# USB_HUB.net
KiCad netlist of a schematic drawn in EasyEDA Pro
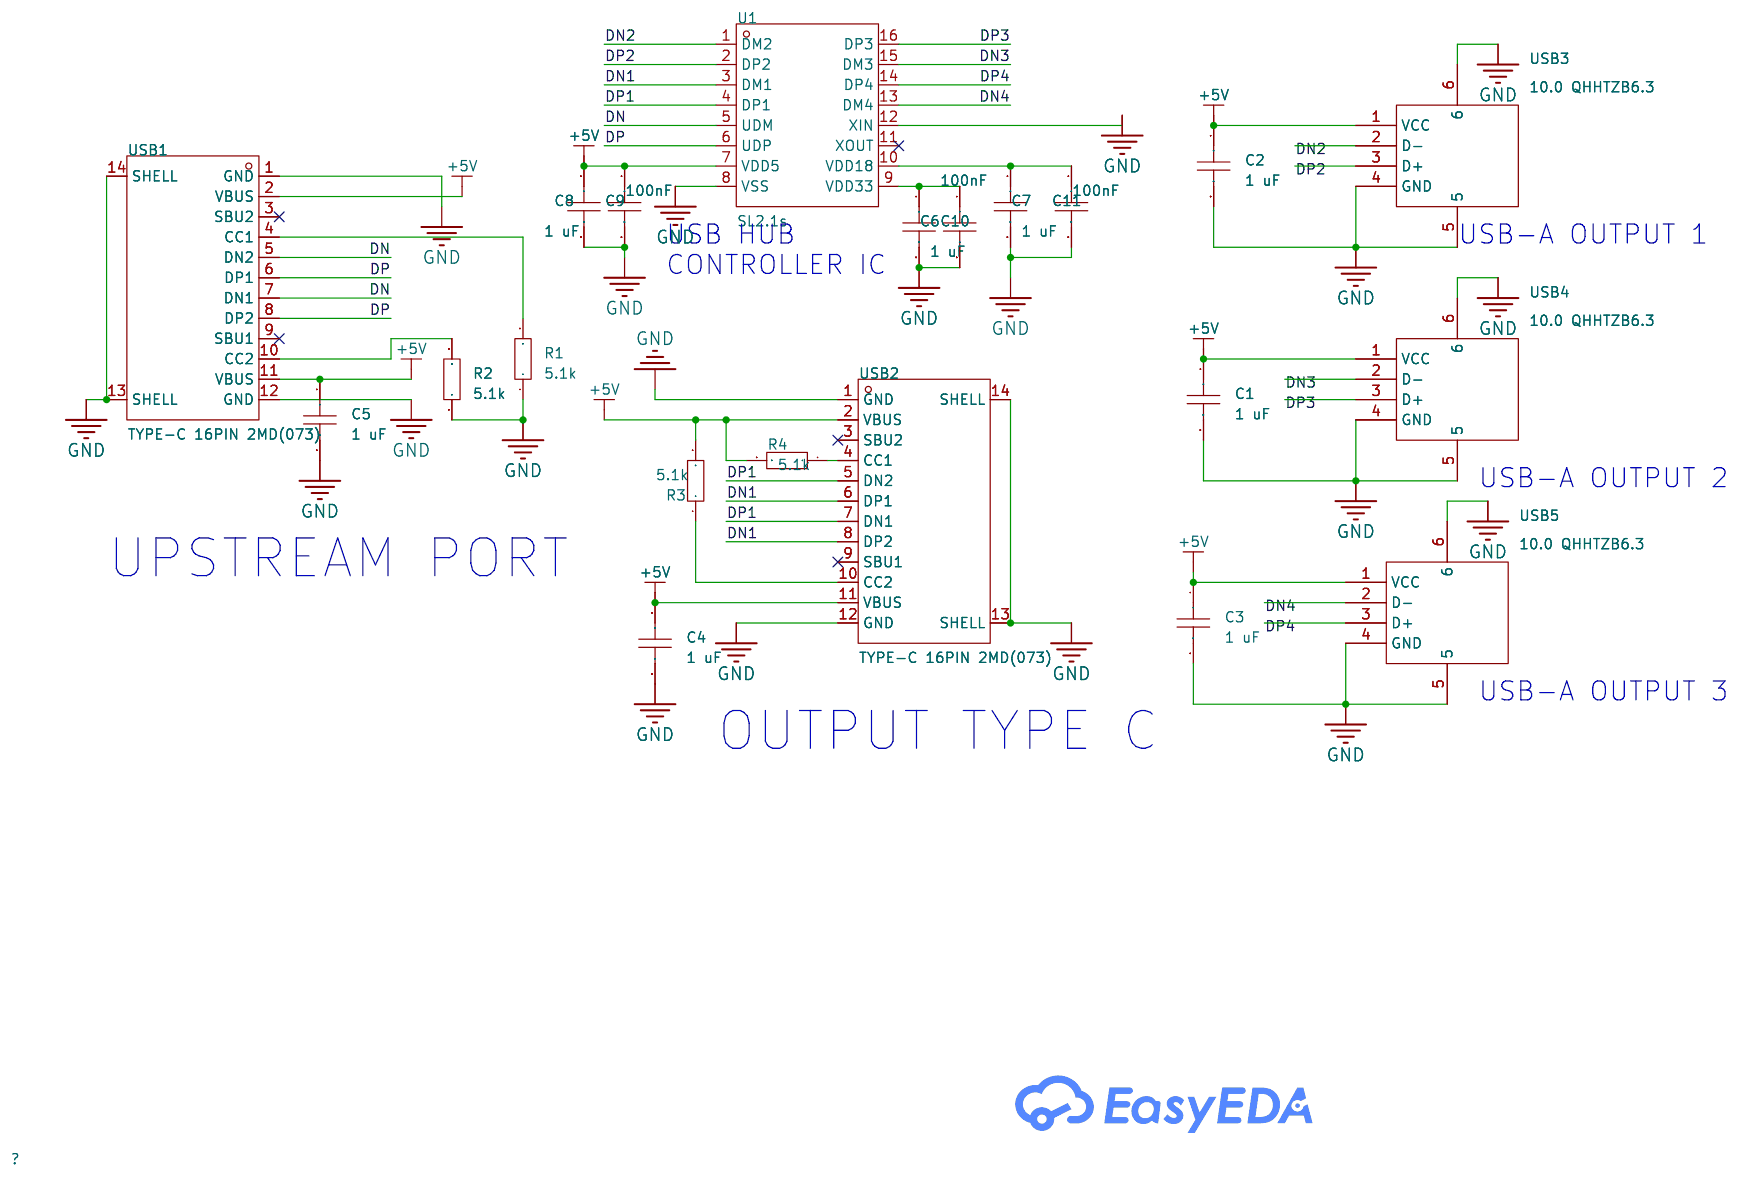
[diagram p0: schematic sheet]

(export (version "E")
  (design (tool "Eeschema 10.0.6"))
  (components
    (comp (ref "C1")
      (value "1 uF")
      (footprint "easyedapro:C0603")
      (libsource (lib "easyedapro") (part "CAP"))
    )
    (comp (ref "C2")
      (value "1 uF")
      (footprint "easyedapro:C0603")
      (libsource (lib "easyedapro") (part "CAP"))
    )
    (comp (ref "C3")
      (value "1 uF")
      (footprint "easyedapro:C0603")
      (libsource (lib "easyedapro") (part "CAP"))
    )
    (comp (ref "C4")
      (value "1 uF")
      (footprint "easyedapro:C0603")
      (libsource (lib "easyedapro") (part "CAP"))
    )
    (comp (ref "C5")
      (value "1 uF")
      (footprint "easyedapro:C0603")
      (libsource (lib "easyedapro") (part "CAP"))
    )
    (comp (ref "C6")
      (value "1 uF")
      (footprint "easyedapro:C0603")
      (libsource (lib "easyedapro") (part "CAP"))
    )
    (comp (ref "C7")
      (value "1 uF")
      (footprint "easyedapro:C0603")
      (libsource (lib "easyedapro") (part "CAP"))
    )
    (comp (ref "C8")
      (value "1 uF")
      (footprint "easyedapro:C0603")
      (libsource (lib "easyedapro") (part "CAP"))
    )
    (comp (ref "C9")
      (value "100nF")
      (footprint "easyedapro:C0603")
      (libsource (lib "easyedapro") (part "CAP"))
    )
    (comp (ref "C10")
      (value "100nF")
      (footprint "easyedapro:C0603")
      (libsource (lib "easyedapro") (part "CAP"))
    )
    (comp (ref "C11")
      (value "100nF")
      (footprint "easyedapro:C0603")
      (libsource (lib "easyedapro") (part "CAP"))
    )
    (comp (ref "R1")
      (value "5.1k")
      (footprint "easyedapro:R0603")
      (libsource (lib "easyedapro") (part "Res"))
    )
    (comp (ref "R2")
      (value "5.1k")
      (footprint "easyedapro:R0603")
      (libsource (lib "easyedapro") (part "Res"))
    )
    (comp (ref "R3")
      (value "5.1k")
      (footprint "easyedapro:R0603")
      (libsource (lib "easyedapro") (part "Res"))
    )
    (comp (ref "R4")
      (value "5.1k")
      (footprint "easyedapro:R0603")
      (libsource (lib "easyedapro") (part "Res"))
    )
    (comp (ref "U1")
      (value "SL2.1s")
      (footprint "easyedapro:SSOP-16_L4.6-W2.6-P0.53-LS4.0-BL")
      (fields (field (name "Manufacturer") "CoreChips(和芯润德)"))
      (libsource (lib "easyedapro") (part "SL2.1S"))
    )
    (comp (ref "USB1")
      (value "TYPE-C 16PIN 2MD(073)")
      (footprint "easyedapro:USB-C-SMD_TYPE-C-6PIN-2MD-073")
      (fields (field (name "Manufacturer") "SHOU HAN(首韩)"))
      (libsource (lib "easyedapro") (part "TYPE-C 16PIN 2MD(073)"))
    )
    (comp (ref "USB2")
      (value "TYPE-C 16PIN 2MD(073)")
      (footprint "easyedapro:USB-C-SMD_TYPE-C-6PIN-2MD-073")
      (fields (field (name "Manufacturer") "SHOU HAN(首韩)"))
      (libsource (lib "easyedapro") (part "TYPE-C 16PIN 2MD(073)"))
    )
    (comp (ref "USB3")
      (value "10.0 QHHTZB6.3")
      (footprint "easyedapro:USB-A-TH_10.0QHHTZB6.3")
      (fields (field (name "Manufacturer") "SHOU HAN(首韩)"))
      (libsource (lib "easyedapro") (part "10.0 QHHTZB6.3"))
    )
    (comp (ref "USB4")
      (value "10.0 QHHTZB6.3")
      (footprint "easyedapro:USB-A-TH_10.0QHHTZB6.3")
      (fields (field (name "Manufacturer") "SHOU HAN(首韩)"))
      (libsource (lib "easyedapro") (part "10.0 QHHTZB6.3"))
    )
    (comp (ref "USB5")
      (value "10.0 QHHTZB6.3")
      (footprint "easyedapro:USB-A-TH_10.0QHHTZB6.3")
      (fields (field (name "Manufacturer") "SHOU HAN(首韩)"))
      (libsource (lib "easyedapro") (part "10.0 QHHTZB6.3"))
    )
  )
  (nets
    (net (code "1") (name "+5V") (class "Default")
      (node (ref "C1") (pin "1") (pinfunction "1_1") (pintype "input"))
      (node (ref "C2") (pin "1") (pinfunction "1_1") (pintype "input"))
      (node (ref "C3") (pin "1") (pinfunction "1_1") (pintype "input"))
      (node (ref "C4") (pin "1") (pinfunction "1_1") (pintype "input"))
      (node (ref "C5") (pin "1") (pinfunction "1_1") (pintype "input"))
      (node (ref "C8") (pin "1") (pinfunction "1_1") (pintype "input"))
      (node (ref "C9") (pin "1") (pinfunction "1_1") (pintype "input"))
      (node (ref "R3") (pin "2") (pinfunction "2_2") (pintype "input"))
      (node (ref "R4") (pin "2") (pinfunction "2_2") (pintype "input"))
      (node (ref "U1") (pin "7") (pinfunction "VDD5_7") (pintype "unspecified"))
      (node (ref "USB1") (pin "11") (pinfunction "VBUS_11") (pintype "unspecified"))
      (node (ref "USB1") (pin "2") (pinfunction "VBUS_2") (pintype "unspecified"))
      (node (ref "USB2") (pin "11") (pinfunction "VBUS_11") (pintype "unspecified"))
      (node (ref "USB2") (pin "2") (pinfunction "VBUS_2") (pintype "unspecified"))
      (node (ref "USB3") (pin "1") (pinfunction "VCC_1") (pintype "unspecified"))
      (node (ref "USB4") (pin "1") (pinfunction "VCC_1") (pintype "unspecified"))
      (node (ref "USB5") (pin "1") (pinfunction "VCC_1") (pintype "unspecified"))
    )
    (net (code "2") (name "/DN") (class "Default")
      (node (ref "U1") (pin "5") (pinfunction "UDM_5") (pintype "unspecified"))
      (node (ref "USB1") (pin "5") (pinfunction "DN2_5") (pintype "unspecified"))
      (node (ref "USB1") (pin "7") (pinfunction "DN1_7") (pintype "unspecified"))
    )
    (net (code "3") (name "/DN1") (class "Default")
      (node (ref "U1") (pin "3") (pinfunction "DM1_3") (pintype "unspecified"))
      (node (ref "USB2") (pin "6") (pinfunction "DP1_6") (pintype "unspecified"))
      (node (ref "USB2") (pin "8") (pinfunction "DP2_8") (pintype "unspecified"))
    )
    (net (code "4") (name "/DN2") (class "Default")
      (node (ref "U1") (pin "1") (pinfunction "DM2_1") (pintype "unspecified"))
      (node (ref "USB3") (pin "2") (pinfunction "D-_2") (pintype "unspecified"))
    )
    (net (code "5") (name "/DN3") (class "Default")
      (node (ref "U1") (pin "15") (pinfunction "DM3_15") (pintype "unspecified"))
      (node (ref "USB4") (pin "2") (pinfunction "D-_2") (pintype "unspecified"))
    )
    (net (code "6") (name "/DN4") (class "Default")
      (node (ref "U1") (pin "13") (pinfunction "DM4_13") (pintype "unspecified"))
      (node (ref "USB5") (pin "2") (pinfunction "D-_2") (pintype "unspecified"))
    )
    (net (code "7") (name "/DP") (class "Default")
      (node (ref "U1") (pin "6") (pinfunction "UDP_6") (pintype "unspecified"))
      (node (ref "USB1") (pin "6") (pinfunction "DP1_6") (pintype "unspecified"))
      (node (ref "USB1") (pin "8") (pinfunction "DP2_8") (pintype "unspecified"))
    )
    (net (code "8") (name "/DP1") (class "Default")
      (node (ref "U1") (pin "4") (pinfunction "DP1_4") (pintype "unspecified"))
      (node (ref "USB2") (pin "5") (pinfunction "DN2_5") (pintype "unspecified"))
      (node (ref "USB2") (pin "7") (pinfunction "DN1_7") (pintype "unspecified"))
    )
    (net (code "9") (name "/DP2") (class "Default")
      (node (ref "U1") (pin "2") (pinfunction "DP2_2") (pintype "unspecified"))
      (node (ref "USB3") (pin "3") (pinfunction "D+_3") (pintype "unspecified"))
    )
    (net (code "10") (name "/DP3") (class "Default")
      (node (ref "U1") (pin "16") (pinfunction "DP3_16") (pintype "unspecified"))
      (node (ref "USB4") (pin "3") (pinfunction "D+_3") (pintype "unspecified"))
    )
    (net (code "11") (name "/DP4") (class "Default")
      (node (ref "U1") (pin "14") (pinfunction "DP4_14") (pintype "unspecified"))
      (node (ref "USB5") (pin "3") (pinfunction "D+_3") (pintype "unspecified"))
    )
    (net (code "12") (name "GND") (class "Default")
      (node (ref "C1") (pin "2") (pinfunction "2_2") (pintype "input"))
      (node (ref "C10") (pin "2") (pinfunction "2_2") (pintype "input"))
      (node (ref "C11") (pin "2") (pinfunction "2_2") (pintype "input"))
      (node (ref "C2") (pin "2") (pinfunction "2_2") (pintype "input"))
      (node (ref "C3") (pin "2") (pinfunction "2_2") (pintype "input"))
      (node (ref "C4") (pin "2") (pinfunction "2_2") (pintype "input"))
      (node (ref "C5") (pin "2") (pinfunction "2_2") (pintype "input"))
      (node (ref "C6") (pin "2") (pinfunction "2_2") (pintype "input"))
      (node (ref "C7") (pin "2") (pinfunction "2_2") (pintype "input"))
      (node (ref "C8") (pin "2") (pinfunction "2_2") (pintype "input"))
      (node (ref "C9") (pin "2") (pinfunction "2_2") (pintype "input"))
      (node (ref "R1") (pin "1") (pinfunction "1_1") (pintype "input"))
      (node (ref "R2") (pin "1") (pinfunction "1_1") (pintype "input"))
      (node (ref "U1") (pin "12") (pinfunction "XIN_12") (pintype "unspecified"))
      (node (ref "U1") (pin "8") (pinfunction "VSS_8") (pintype "unspecified"))
      (node (ref "USB1") (pin "1") (pinfunction "GND_1") (pintype "unspecified"))
      (node (ref "USB1") (pin "12") (pinfunction "GND_12") (pintype "unspecified"))
      (node (ref "USB1") (pin "13") (pinfunction "SHELL_13") (pintype "unspecified"))
      (node (ref "USB1") (pin "14") (pinfunction "SHELL_14") (pintype "unspecified"))
      (node (ref "USB2") (pin "1") (pinfunction "GND_1") (pintype "unspecified"))
      (node (ref "USB2") (pin "12") (pinfunction "GND_12") (pintype "unspecified"))
      (node (ref "USB2") (pin "13") (pinfunction "SHELL_13") (pintype "unspecified"))
      (node (ref "USB2") (pin "14") (pinfunction "SHELL_14") (pintype "unspecified"))
      (node (ref "USB3") (pin "4") (pinfunction "GND_4") (pintype "unspecified"))
      (node (ref "USB3") (pin "5") (pinfunction "5_5") (pintype "unspecified"))
      (node (ref "USB3") (pin "6") (pinfunction "6_6") (pintype "unspecified"))
      (node (ref "USB4") (pin "4") (pinfunction "GND_4") (pintype "unspecified"))
      (node (ref "USB4") (pin "5") (pinfunction "5_5") (pintype "unspecified"))
      (node (ref "USB4") (pin "6") (pinfunction "6_6") (pintype "unspecified"))
      (node (ref "USB5") (pin "4") (pinfunction "GND_4") (pintype "unspecified"))
      (node (ref "USB5") (pin "5") (pinfunction "5_5") (pintype "unspecified"))
      (node (ref "USB5") (pin "6") (pinfunction "6_6") (pintype "unspecified"))
    )
    (net (code "13") (name "Net-(U1-VDD18)") (class "Default")
      (node (ref "C11") (pin "1") (pinfunction "1_1") (pintype "input"))
      (node (ref "C7") (pin "1") (pinfunction "1_1") (pintype "input"))
      (node (ref "U1") (pin "10") (pinfunction "VDD18_10") (pintype "unspecified"))
    )
    (net (code "14") (name "Net-(U1-VDD33)") (class "Default")
      (node (ref "C10") (pin "1") (pinfunction "1_1") (pintype "input"))
      (node (ref "C6") (pin "1") (pinfunction "1_1") (pintype "input"))
      (node (ref "U1") (pin "9") (pinfunction "VDD33_9") (pintype "unspecified"))
    )
    (net (code "15") (name "Net-(USB1-CC1)") (class "Default")
      (node (ref "R1") (pin "2") (pinfunction "2_2") (pintype "input"))
      (node (ref "USB1") (pin "4") (pinfunction "CC1_4") (pintype "unspecified"))
    )
    (net (code "16") (name "Net-(USB1-CC2)") (class "Default")
      (node (ref "R2") (pin "2") (pinfunction "2_2") (pintype "input"))
      (node (ref "USB1") (pin "10") (pinfunction "CC2_10") (pintype "unspecified"))
    )
    (net (code "17") (name "Net-(USB2-CC1)") (class "Default")
      (node (ref "R4") (pin "1") (pinfunction "1_1") (pintype "input"))
      (node (ref "USB2") (pin "4") (pinfunction "CC1_4") (pintype "unspecified"))
    )
    (net (code "18") (name "Net-(USB2-CC2)") (class "Default")
      (node (ref "R3") (pin "1") (pinfunction "1_1") (pintype "input"))
      (node (ref "USB2") (pin "10") (pinfunction "CC2_10") (pintype "unspecified"))
    )
    (net (code "19") (name "unconnected-(U1-XOUT-Pad11)") (class "Default")
      (node (ref "U1") (pin "11") (pinfunction "XOUT_11") (pintype "unspecified+no_connect"))
    )
    (net (code "20") (name "unconnected-(USB1-SBU1-Pad9)") (class "Default")
      (node (ref "USB1") (pin "9") (pinfunction "SBU1_9") (pintype "unspecified+no_connect"))
    )
    (net (code "21") (name "unconnected-(USB1-SBU2-Pad3)") (class "Default")
      (node (ref "USB1") (pin "3") (pinfunction "SBU2_3") (pintype "unspecified+no_connect"))
    )
    (net (code "22") (name "unconnected-(USB2-SBU1-Pad9)") (class "Default")
      (node (ref "USB2") (pin "9") (pinfunction "SBU1_9") (pintype "unspecified+no_connect"))
    )
    (net (code "23") (name "unconnected-(USB2-SBU2-Pad3)") (class "Default")
      (node (ref "USB2") (pin "3") (pinfunction "SBU2_3") (pintype "unspecified+no_connect"))
    )
  )
)
